# CD74HC4067_MUX.net
KiCad netlist of a schematic drawn in Altium Designer
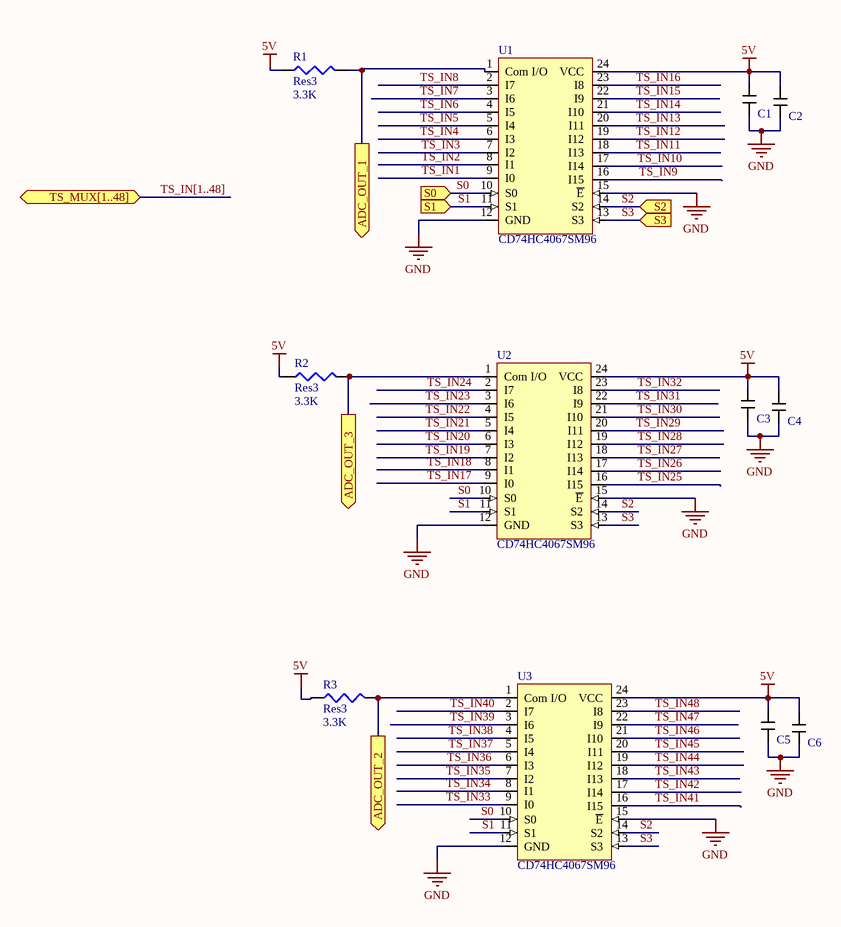
[diagram p0: CD74HC4067_MUX.SchDoc]

(export (version "E")
  (design (tool "Eeschema 10.0.6"))
  (components
    (comp (ref "C1")
      (value "0.1uF Cap")
      (footprint "0.1uF_Kemet")
      (description "C0603C101K8GAC7867 Kemet Capacitor")
      (libsource (lib "0.1_uF_Kemet_Cap") (part "0.1uF Cap"))
    )
    (comp (ref "C2")
      (value "1uF Samsung Cap")
      (footprint "1uf_Samsung")
      (libsource (lib "1uF_Samsung_Cap") (part "1uF Samsung Cap"))
    )
    (comp (ref "C3")
      (value "0.1uF Cap")
      (footprint "0.1uF_Kemet")
      (description "C0603C101K8GAC7867 Kemet Capacitor")
      (libsource (lib "0.1_uF_Kemet_Cap") (part "0.1uF Cap"))
    )
    (comp (ref "C4")
      (value "1uF Samsung Cap")
      (footprint "1uf_Samsung")
      (libsource (lib "1uF_Samsung_Cap") (part "1uF Samsung Cap"))
    )
    (comp (ref "C5")
      (value "0.1uF Cap")
      (footprint "0.1uF_Kemet")
      (description "C0603C101K8GAC7867 Kemet Capacitor")
      (libsource (lib "0.1_uF_Kemet_Cap") (part "0.1uF Cap"))
    )
    (comp (ref "C6")
      (value "1uF Samsung Cap")
      (footprint "1uf_Samsung")
      (libsource (lib "1uF_Samsung_Cap") (part "1uF Samsung Cap"))
    )
    (comp (ref "R1")
      (value "Res3")
      (footprint "J1-0603")
      (description "Resistor")
      (fields (field (name "ALTIUM_VALUE") "3.3K") (field (name "PUBLISHER") "Altium Limited"))
      (libsource (lib "Miscellaneous Devices") (part "Res3"))
    )
    (comp (ref "R2")
      (value "Res3")
      (footprint "J1-0603")
      (description "Resistor")
      (fields (field (name "ALTIUM_VALUE") "3.3K") (field (name "PUBLISHER") "Altium Limited"))
      (libsource (lib "Miscellaneous Devices") (part "Res3"))
    )
    (comp (ref "R3")
      (value "Res3")
      (footprint "J1-0603")
      (description "Resistor")
      (fields (field (name "ALTIUM_VALUE") "3.3K") (field (name "PUBLISHER") "Altium Limited"))
      (libsource (lib "Miscellaneous Devices") (part "Res3"))
    )
    (comp (ref "U1")
      (value "CD74HC4067SM96")
      (footprint "SOIC-24_MUX")
      (libsource (lib "TI_Mux") (part "CD74HC4067SM96"))
    )
    (comp (ref "U2")
      (value "CD74HC4067SM96")
      (footprint "SOIC-24_MUX")
      (libsource (lib "TI_Mux") (part "CD74HC4067SM96"))
    )
    (comp (ref "U3")
      (value "CD74HC4067SM96")
      (footprint "SOIC-24_MUX")
      (libsource (lib "TI_Mux") (part "CD74HC4067SM96"))
    )
  )
  (nets
    (net (code "1") (name "/ADC_OUT_1") (class "Default")
      (node (ref "R1") (pin "2") (pinfunction "2_2") (pintype "passive"))
      (node (ref "U1") (pin "1") (pinfunction "Com_I/O_1") (pintype "bidirectional"))
    )
    (net (code "2") (name "/ADC_OUT_2") (class "Default")
      (node (ref "R3") (pin "2") (pinfunction "2_2") (pintype "passive"))
      (node (ref "U3") (pin "1") (pinfunction "Com_I/O_1") (pintype "bidirectional"))
    )
    (net (code "3") (name "/ADC_OUT_3") (class "Default")
      (node (ref "R2") (pin "2") (pinfunction "2_2") (pintype "passive"))
      (node (ref "U2") (pin "1") (pinfunction "Com_I/O_1") (pintype "bidirectional"))
    )
    (net (code "4") (name "/S0") (class "Default")
      (node (ref "U1") (pin "10") (pinfunction "S0_10") (pintype "input"))
      (node (ref "U2") (pin "10") (pinfunction "S0_10") (pintype "input"))
      (node (ref "U3") (pin "10") (pinfunction "S0_10") (pintype "input"))
    )
    (net (code "5") (name "/S1") (class "Default")
      (node (ref "U1") (pin "11") (pinfunction "S1_11") (pintype "input"))
      (node (ref "U2") (pin "11") (pinfunction "S1_11") (pintype "input"))
      (node (ref "U3") (pin "11") (pinfunction "S1_11") (pintype "input"))
    )
    (net (code "6") (name "/S2") (class "Default")
      (node (ref "U1") (pin "14") (pinfunction "S2_14") (pintype "input"))
      (node (ref "U2") (pin "14") (pinfunction "S2_14") (pintype "input"))
      (node (ref "U3") (pin "14") (pinfunction "S2_14") (pintype "input"))
    )
    (net (code "7") (name "/S3") (class "Default")
      (node (ref "U1") (pin "13") (pinfunction "S3_13") (pintype "input"))
      (node (ref "U2") (pin "13") (pinfunction "S3_13") (pintype "input"))
      (node (ref "U3") (pin "13") (pinfunction "S3_13") (pintype "input"))
    )
    (net (code "8") (name "/TS_IN1") (class "Default")
      (node (ref "U1") (pin "9") (pinfunction "I0_9") (pintype "passive"))
    )
    (net (code "9") (name "/TS_IN2") (class "Default")
      (node (ref "U1") (pin "8") (pinfunction "I1_8") (pintype "passive"))
    )
    (net (code "10") (name "/TS_IN3") (class "Default")
      (node (ref "U1") (pin "7") (pinfunction "I2_7") (pintype "passive"))
    )
    (net (code "11") (name "/TS_IN4") (class "Default")
      (node (ref "U1") (pin "6") (pinfunction "I3_6") (pintype "passive"))
    )
    (net (code "12") (name "/TS_IN5") (class "Default")
      (node (ref "U1") (pin "5") (pinfunction "I4_5") (pintype "passive"))
    )
    (net (code "13") (name "/TS_IN6") (class "Default")
      (node (ref "U1") (pin "4") (pinfunction "I5_4") (pintype "passive"))
    )
    (net (code "14") (name "/TS_IN7") (class "Default")
      (node (ref "U1") (pin "3") (pinfunction "I6_3") (pintype "passive"))
    )
    (net (code "15") (name "/TS_IN8") (class "Default")
      (node (ref "U1") (pin "2") (pinfunction "I7_2") (pintype "passive"))
    )
    (net (code "16") (name "/TS_IN9") (class "Default")
      (node (ref "U1") (pin "16") (pinfunction "I15_16") (pintype "passive"))
    )
    (net (code "17") (name "/TS_IN10") (class "Default")
      (node (ref "U1") (pin "17") (pinfunction "I14_17") (pintype "passive"))
    )
    (net (code "18") (name "/TS_IN11") (class "Default")
      (node (ref "U1") (pin "18") (pinfunction "I13_18") (pintype "passive"))
    )
    (net (code "19") (name "/TS_IN12") (class "Default")
      (node (ref "U1") (pin "19") (pinfunction "I12_19") (pintype "passive"))
    )
    (net (code "20") (name "/TS_IN13") (class "Default")
      (node (ref "U1") (pin "20") (pinfunction "I11_20") (pintype "passive"))
    )
    (net (code "21") (name "/TS_IN14") (class "Default")
      (node (ref "U1") (pin "21") (pinfunction "I10_21") (pintype "passive"))
    )
    (net (code "22") (name "/TS_IN15") (class "Default")
      (node (ref "U1") (pin "22") (pinfunction "I9_22") (pintype "passive"))
    )
    (net (code "23") (name "/TS_IN16") (class "Default")
      (node (ref "U1") (pin "23") (pinfunction "I8_23") (pintype "passive"))
    )
    (net (code "24") (name "/TS_IN17") (class "Default")
      (node (ref "U2") (pin "9") (pinfunction "I0_9") (pintype "passive"))
    )
    (net (code "25") (name "/TS_IN18") (class "Default")
      (node (ref "U2") (pin "8") (pinfunction "I1_8") (pintype "passive"))
    )
    (net (code "26") (name "/TS_IN19") (class "Default")
      (node (ref "U2") (pin "7") (pinfunction "I2_7") (pintype "passive"))
    )
    (net (code "27") (name "/TS_IN20") (class "Default")
      (node (ref "U2") (pin "6") (pinfunction "I3_6") (pintype "passive"))
    )
    (net (code "28") (name "/TS_IN21") (class "Default")
      (node (ref "U2") (pin "5") (pinfunction "I4_5") (pintype "passive"))
    )
    (net (code "29") (name "/TS_IN22") (class "Default")
      (node (ref "U2") (pin "4") (pinfunction "I5_4") (pintype "passive"))
    )
    (net (code "30") (name "/TS_IN23") (class "Default")
      (node (ref "U2") (pin "3") (pinfunction "I6_3") (pintype "passive"))
    )
    (net (code "31") (name "/TS_IN24") (class "Default")
      (node (ref "U2") (pin "2") (pinfunction "I7_2") (pintype "passive"))
    )
    (net (code "32") (name "/TS_IN25") (class "Default")
      (node (ref "U2") (pin "16") (pinfunction "I15_16") (pintype "passive"))
    )
    (net (code "33") (name "/TS_IN26") (class "Default")
      (node (ref "U2") (pin "17") (pinfunction "I14_17") (pintype "passive"))
    )
    (net (code "34") (name "/TS_IN27") (class "Default")
      (node (ref "U2") (pin "18") (pinfunction "I13_18") (pintype "passive"))
    )
    (net (code "35") (name "/TS_IN28") (class "Default")
      (node (ref "U2") (pin "19") (pinfunction "I12_19") (pintype "passive"))
    )
    (net (code "36") (name "/TS_IN29") (class "Default")
      (node (ref "U2") (pin "20") (pinfunction "I11_20") (pintype "passive"))
    )
    (net (code "37") (name "/TS_IN30") (class "Default")
      (node (ref "U2") (pin "21") (pinfunction "I10_21") (pintype "passive"))
    )
    (net (code "38") (name "/TS_IN31") (class "Default")
      (node (ref "U2") (pin "22") (pinfunction "I9_22") (pintype "passive"))
    )
    (net (code "39") (name "/TS_IN32") (class "Default")
      (node (ref "U2") (pin "23") (pinfunction "I8_23") (pintype "passive"))
    )
    (net (code "40") (name "/TS_IN33") (class "Default")
      (node (ref "U3") (pin "9") (pinfunction "I0_9") (pintype "passive"))
    )
    (net (code "41") (name "/TS_IN34") (class "Default")
      (node (ref "U3") (pin "8") (pinfunction "I1_8") (pintype "passive"))
    )
    (net (code "42") (name "/TS_IN35") (class "Default")
      (node (ref "U3") (pin "7") (pinfunction "I2_7") (pintype "passive"))
    )
    (net (code "43") (name "/TS_IN36") (class "Default")
      (node (ref "U3") (pin "6") (pinfunction "I3_6") (pintype "passive"))
    )
    (net (code "44") (name "/TS_IN37") (class "Default")
      (node (ref "U3") (pin "5") (pinfunction "I4_5") (pintype "passive"))
    )
    (net (code "45") (name "/TS_IN38") (class "Default")
      (node (ref "U3") (pin "4") (pinfunction "I5_4") (pintype "passive"))
    )
    (net (code "46") (name "/TS_IN39") (class "Default")
      (node (ref "U3") (pin "3") (pinfunction "I6_3") (pintype "passive"))
    )
    (net (code "47") (name "/TS_IN40") (class "Default")
      (node (ref "U3") (pin "2") (pinfunction "I7_2") (pintype "passive"))
    )
    (net (code "48") (name "/TS_IN41") (class "Default")
      (node (ref "U3") (pin "16") (pinfunction "I15_16") (pintype "passive"))
    )
    (net (code "49") (name "/TS_IN42") (class "Default")
      (node (ref "U3") (pin "17") (pinfunction "I14_17") (pintype "passive"))
    )
    (net (code "50") (name "/TS_IN43") (class "Default")
      (node (ref "U3") (pin "18") (pinfunction "I13_18") (pintype "passive"))
    )
    (net (code "51") (name "/TS_IN44") (class "Default")
      (node (ref "U3") (pin "19") (pinfunction "I12_19") (pintype "passive"))
    )
    (net (code "52") (name "/TS_IN45") (class "Default")
      (node (ref "U3") (pin "20") (pinfunction "I11_20") (pintype "passive"))
    )
    (net (code "53") (name "/TS_IN46") (class "Default")
      (node (ref "U3") (pin "21") (pinfunction "I10_21") (pintype "passive"))
    )
    (net (code "54") (name "/TS_IN47") (class "Default")
      (node (ref "U3") (pin "22") (pinfunction "I9_22") (pintype "passive"))
    )
    (net (code "55") (name "/TS_IN48") (class "Default")
      (node (ref "U3") (pin "23") (pinfunction "I8_23") (pintype "passive"))
    )
    (net (code "57") (name "5V") (class "Default")
      (node (ref "C1") (pin "2") (pinfunction "2_2") (pintype "passive"))
      (node (ref "C2") (pin "2") (pinfunction "2_2") (pintype "passive"))
      (node (ref "C3") (pin "2") (pinfunction "2_2") (pintype "passive"))
      (node (ref "C4") (pin "2") (pinfunction "2_2") (pintype "passive"))
      (node (ref "C5") (pin "2") (pinfunction "2_2") (pintype "passive"))
      (node (ref "C6") (pin "2") (pinfunction "2_2") (pintype "passive"))
      (node (ref "R1") (pin "1") (pinfunction "1_1") (pintype "passive"))
      (node (ref "R2") (pin "1") (pinfunction "1_1") (pintype "passive"))
      (node (ref "R3") (pin "1") (pinfunction "1_1") (pintype "passive"))
      (node (ref "U1") (pin "24") (pinfunction "VCC_24") (pintype "power_in"))
      (node (ref "U2") (pin "24") (pinfunction "VCC_24") (pintype "power_in"))
      (node (ref "U3") (pin "24") (pinfunction "VCC_24") (pintype "power_in"))
    )
    (net (code "58") (name "GND") (class "Default")
      (node (ref "C1") (pin "1") (pinfunction "1_1") (pintype "passive"))
      (node (ref "C2") (pin "1") (pinfunction "1_1") (pintype "passive"))
      (node (ref "C3") (pin "1") (pinfunction "1_1") (pintype "passive"))
      (node (ref "C4") (pin "1") (pinfunction "1_1") (pintype "passive"))
      (node (ref "C5") (pin "1") (pinfunction "1_1") (pintype "passive"))
      (node (ref "C6") (pin "1") (pinfunction "1_1") (pintype "passive"))
      (node (ref "U1") (pin "12") (pinfunction "GND_12") (pintype "power_in"))
      (node (ref "U1") (pin "15") (pinfunction "~{E}_15") (pintype "input"))
      (node (ref "U2") (pin "12") (pinfunction "GND_12") (pintype "power_in"))
      (node (ref "U2") (pin "15") (pinfunction "~{E}_15") (pintype "input"))
      (node (ref "U3") (pin "12") (pinfunction "GND_12") (pintype "power_in"))
      (node (ref "U3") (pin "15") (pinfunction "~{E}_15") (pintype "input"))
    )
  )
)
